# DDR3L.net
KiCad netlist of a schematic drawn in Altium Designer
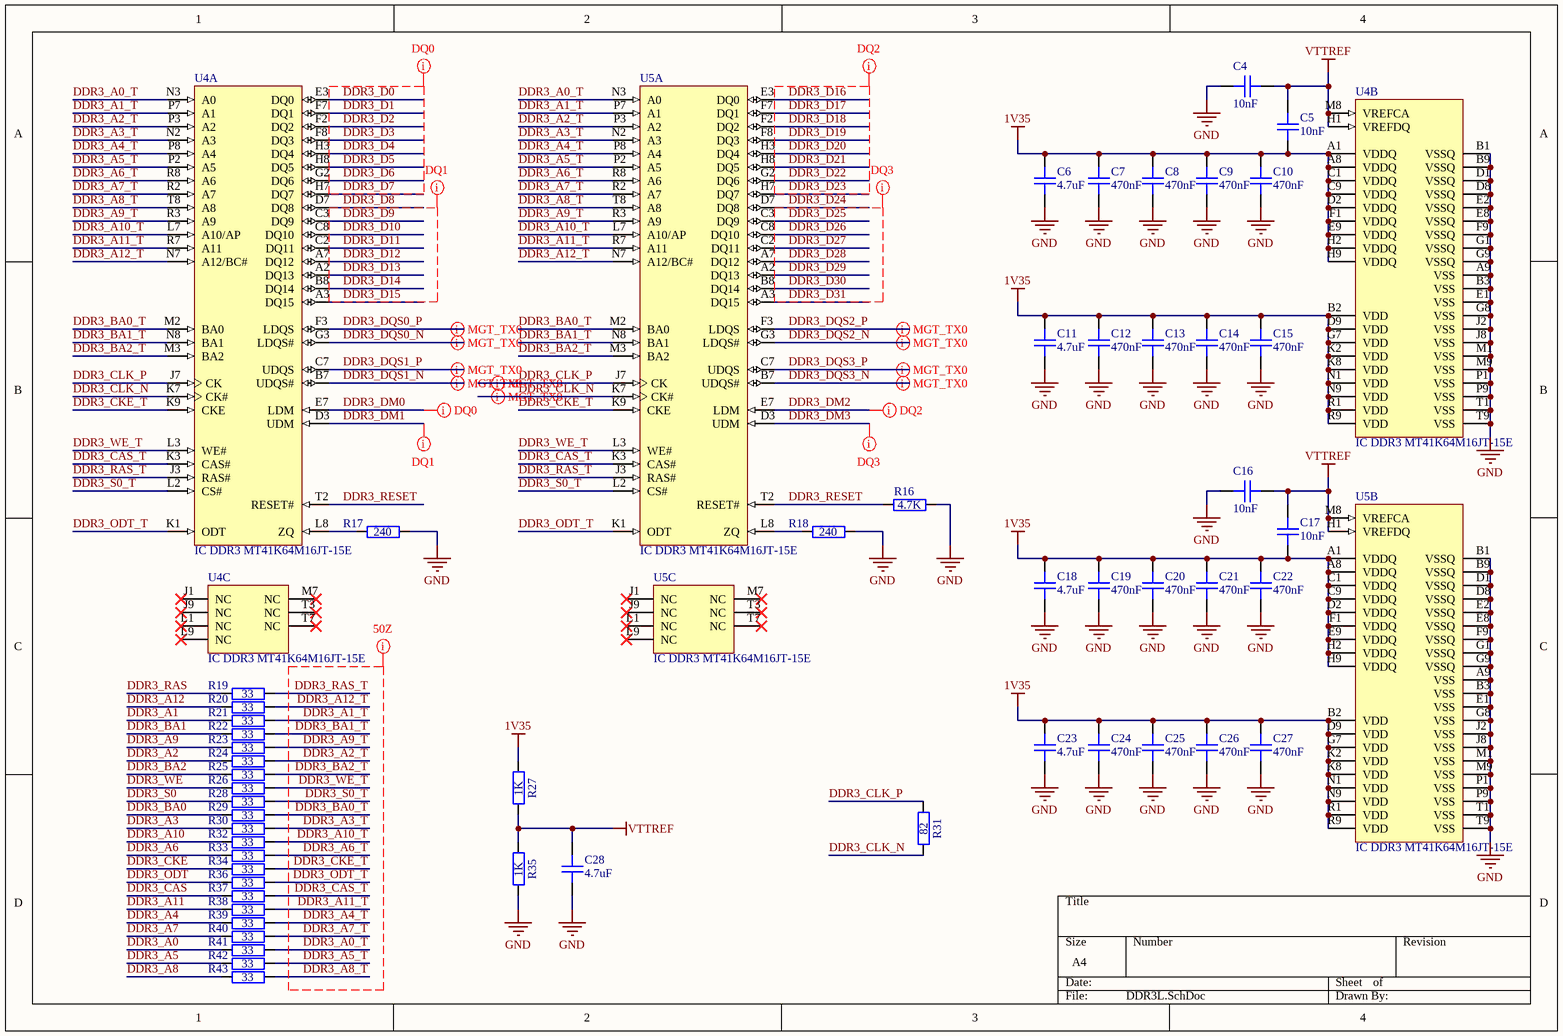
[diagram p0: DDR3L.SchDoc]

(export (version "E")
  (design (tool "Eeschema 10.0.6"))
  (components
    (comp (ref "C4")
      (value "10nF")
      (footprint "GEN_C_0402")
      (libsource (lib "DSO") (part "CAP 10nF 50V X7R 0402"))
    )
    (comp (ref "C5")
      (value "10nF")
      (footprint "GEN_C_0402")
      (libsource (lib "DSO") (part "CAP 10nF 50V X7R 0402"))
    )
    (comp (ref "C6")
      (value "4.7uF")
      (footprint "GEN_C_0402")
      (libsource (lib "DSO") (part "CAP 4.7uF 6.3V X5R 0402"))
    )
    (comp (ref "C7")
      (value "470nF")
      (footprint "GEN_C_0201")
      (libsource (lib "DSO") (part "CAP 470nF 6.3V X5R 0201"))
    )
    (comp (ref "C8")
      (value "470nF")
      (footprint "GEN_C_0201")
      (libsource (lib "DSO") (part "CAP 470nF 6.3V X5R 0201"))
    )
    (comp (ref "C9")
      (value "470nF")
      (footprint "GEN_C_0201")
      (libsource (lib "DSO") (part "CAP 470nF 6.3V X5R 0201"))
    )
    (comp (ref "C10")
      (value "470nF")
      (footprint "GEN_C_0201")
      (libsource (lib "DSO") (part "CAP 470nF 6.3V X5R 0201"))
    )
    (comp (ref "C11")
      (value "4.7uF")
      (footprint "GEN_C_0402")
      (libsource (lib "DSO") (part "CAP 4.7uF 6.3V X5R 0402"))
    )
    (comp (ref "C12")
      (value "470nF")
      (footprint "GEN_C_0201")
      (libsource (lib "DSO") (part "CAP 470nF 6.3V X5R 0201"))
    )
    (comp (ref "C13")
      (value "470nF")
      (footprint "GEN_C_0201")
      (libsource (lib "DSO") (part "CAP 470nF 6.3V X5R 0201"))
    )
    (comp (ref "C14")
      (value "470nF")
      (footprint "GEN_C_0201")
      (libsource (lib "DSO") (part "CAP 470nF 6.3V X5R 0201"))
    )
    (comp (ref "C15")
      (value "470nF")
      (footprint "GEN_C_0201")
      (libsource (lib "DSO") (part "CAP 470nF 6.3V X5R 0201"))
    )
    (comp (ref "C16")
      (value "10nF")
      (footprint "GEN_C_0402")
      (libsource (lib "DSO") (part "CAP 10nF 50V X7R 0402"))
    )
    (comp (ref "C17")
      (value "10nF")
      (footprint "GEN_C_0402")
      (libsource (lib "DSO") (part "CAP 10nF 50V X7R 0402"))
    )
    (comp (ref "C18")
      (value "4.7uF")
      (footprint "GEN_C_0402")
      (libsource (lib "DSO") (part "CAP 4.7uF 6.3V X5R 0402"))
    )
    (comp (ref "C19")
      (value "470nF")
      (footprint "GEN_C_0201")
      (libsource (lib "DSO") (part "CAP 470nF 6.3V X5R 0201"))
    )
    (comp (ref "C20")
      (value "470nF")
      (footprint "GEN_C_0201")
      (libsource (lib "DSO") (part "CAP 470nF 6.3V X5R 0201"))
    )
    (comp (ref "C21")
      (value "470nF")
      (footprint "GEN_C_0201")
      (libsource (lib "DSO") (part "CAP 470nF 6.3V X5R 0201"))
    )
    (comp (ref "C22")
      (value "470nF")
      (footprint "GEN_C_0201")
      (libsource (lib "DSO") (part "CAP 470nF 6.3V X5R 0201"))
    )
    (comp (ref "C23")
      (value "4.7uF")
      (footprint "GEN_C_0402")
      (libsource (lib "DSO") (part "CAP 4.7uF 6.3V X5R 0402"))
    )
    (comp (ref "C24")
      (value "470nF")
      (footprint "GEN_C_0201")
      (libsource (lib "DSO") (part "CAP 470nF 6.3V X5R 0201"))
    )
    (comp (ref "C25")
      (value "470nF")
      (footprint "GEN_C_0201")
      (libsource (lib "DSO") (part "CAP 470nF 6.3V X5R 0201"))
    )
    (comp (ref "C26")
      (value "470nF")
      (footprint "GEN_C_0201")
      (libsource (lib "DSO") (part "CAP 470nF 6.3V X5R 0201"))
    )
    (comp (ref "C27")
      (value "470nF")
      (footprint "GEN_C_0201")
      (libsource (lib "DSO") (part "CAP 470nF 6.3V X5R 0201"))
    )
    (comp (ref "C28")
      (value "4.7uF")
      (footprint "GEN_C_0402")
      (libsource (lib "DSO") (part "CAP 4.7uF 6.3V X5R 0402"))
    )
    (comp (ref "R16")
      (value "4.7K")
      (footprint "GEN_R_0201")
      (fields (field (name "TOLERANCE") "1%"))
      (libsource (lib "DSO") (part "RES 4.7K OHM 1% 1/20W 0201"))
    )
    (comp (ref "R17")
      (value "240")
      (footprint "GEN_R_0402")
      (fields (field (name "TOLERANCE") "1%"))
      (libsource (lib "DSO") (part "RES 240 OHM 1% 1/16W 0402"))
    )
    (comp (ref "R18")
      (value "240")
      (footprint "GEN_R_0402")
      (fields (field (name "TOLERANCE") "1%"))
      (libsource (lib "DSO") (part "RES 240 OHM 1% 1/16W 0402"))
    )
    (comp (ref "R19")
      (value "33")
      (footprint "GEN_R_0201")
      (fields (field (name "TOLERANCE") "1%"))
      (libsource (lib "DSO") (part "RES 33 OHM 1% 1/20W 0201"))
    )
    (comp (ref "R20")
      (value "33")
      (footprint "GEN_R_0201")
      (fields (field (name "TOLERANCE") "1%"))
      (libsource (lib "DSO") (part "RES 33 OHM 1% 1/20W 0201"))
    )
    (comp (ref "R21")
      (value "33")
      (footprint "GEN_R_0201")
      (fields (field (name "TOLERANCE") "1%"))
      (libsource (lib "DSO") (part "RES 33 OHM 1% 1/20W 0201"))
    )
    (comp (ref "R22")
      (value "33")
      (footprint "GEN_R_0201")
      (fields (field (name "TOLERANCE") "1%"))
      (libsource (lib "DSO") (part "RES 33 OHM 1% 1/20W 0201"))
    )
    (comp (ref "R23")
      (value "33")
      (footprint "GEN_R_0201")
      (fields (field (name "TOLERANCE") "1%"))
      (libsource (lib "DSO") (part "RES 33 OHM 1% 1/20W 0201"))
    )
    (comp (ref "R24")
      (value "33")
      (footprint "GEN_R_0201")
      (fields (field (name "TOLERANCE") "1%"))
      (libsource (lib "DSO") (part "RES 33 OHM 1% 1/20W 0201"))
    )
    (comp (ref "R25")
      (value "33")
      (footprint "GEN_R_0201")
      (fields (field (name "TOLERANCE") "1%"))
      (libsource (lib "DSO") (part "RES 33 OHM 1% 1/20W 0201"))
    )
    (comp (ref "R26")
      (value "33")
      (footprint "GEN_R_0201")
      (fields (field (name "TOLERANCE") "1%"))
      (libsource (lib "DSO") (part "RES 33 OHM 1% 1/20W 0201"))
    )
    (comp (ref "R27")
      (value "1K")
      (footprint "GEN_R_0402")
      (fields (field (name "TOLERANCE") "1%"))
      (libsource (lib "DSO") (part "RES 1K OHM 1% 1/10W 0402"))
    )
    (comp (ref "R28")
      (value "33")
      (footprint "GEN_R_0201")
      (fields (field (name "TOLERANCE") "1%"))
      (libsource (lib "DSO") (part "RES 33 OHM 1% 1/20W 0201"))
    )
    (comp (ref "R29")
      (value "33")
      (footprint "GEN_R_0201")
      (fields (field (name "TOLERANCE") "1%"))
      (libsource (lib "DSO") (part "RES 33 OHM 1% 1/20W 0201"))
    )
    (comp (ref "R30")
      (value "33")
      (footprint "GEN_R_0201")
      (fields (field (name "TOLERANCE") "1%"))
      (libsource (lib "DSO") (part "RES 33 OHM 1% 1/20W 0201"))
    )
    (comp (ref "R31")
      (value "82")
      (footprint "GEN_R_0402")
      (fields (field (name "TOLERANCE") "1%"))
      (libsource (lib "DSO") (part "RES 82 OHM 1% 1/16W 0402"))
    )
    (comp (ref "R32")
      (value "33")
      (footprint "GEN_R_0201")
      (fields (field (name "TOLERANCE") "1%"))
      (libsource (lib "DSO") (part "RES 33 OHM 1% 1/20W 0201"))
    )
    (comp (ref "R33")
      (value "33")
      (footprint "GEN_R_0201")
      (fields (field (name "TOLERANCE") "1%"))
      (libsource (lib "DSO") (part "RES 33 OHM 1% 1/20W 0201"))
    )
    (comp (ref "R34")
      (value "33")
      (footprint "GEN_R_0201")
      (fields (field (name "TOLERANCE") "1%"))
      (libsource (lib "DSO") (part "RES 33 OHM 1% 1/20W 0201"))
    )
    (comp (ref "R35")
      (value "1K")
      (footprint "GEN_R_0402")
      (fields (field (name "TOLERANCE") "1%"))
      (libsource (lib "DSO") (part "RES 1K OHM 1% 1/10W 0402"))
    )
    (comp (ref "R36")
      (value "33")
      (footprint "GEN_R_0201")
      (fields (field (name "TOLERANCE") "1%"))
      (libsource (lib "DSO") (part "RES 33 OHM 1% 1/20W 0201"))
    )
    (comp (ref "R37")
      (value "33")
      (footprint "GEN_R_0201")
      (fields (field (name "TOLERANCE") "1%"))
      (libsource (lib "DSO") (part "RES 33 OHM 1% 1/20W 0201"))
    )
    (comp (ref "R38")
      (value "33")
      (footprint "GEN_R_0201")
      (fields (field (name "TOLERANCE") "1%"))
      (libsource (lib "DSO") (part "RES 33 OHM 1% 1/20W 0201"))
    )
    (comp (ref "R39")
      (value "33")
      (footprint "GEN_R_0201")
      (fields (field (name "TOLERANCE") "1%"))
      (libsource (lib "DSO") (part "RES 33 OHM 1% 1/20W 0201"))
    )
    (comp (ref "R40")
      (value "33")
      (footprint "GEN_R_0201")
      (fields (field (name "TOLERANCE") "1%"))
      (libsource (lib "DSO") (part "RES 33 OHM 1% 1/20W 0201"))
    )
    (comp (ref "R41")
      (value "33")
      (footprint "GEN_R_0201")
      (fields (field (name "TOLERANCE") "1%"))
      (libsource (lib "DSO") (part "RES 33 OHM 1% 1/20W 0201"))
    )
    (comp (ref "R42")
      (value "33")
      (footprint "GEN_R_0201")
      (fields (field (name "TOLERANCE") "1%"))
      (libsource (lib "DSO") (part "RES 33 OHM 1% 1/20W 0201"))
    )
    (comp (ref "R43")
      (value "33")
      (footprint "GEN_R_0201")
      (fields (field (name "TOLERANCE") "1%"))
      (libsource (lib "DSO") (part "RES 33 OHM 1% 1/20W 0201"))
    )
    (comp (ref "U4")
      (value "IC DDR3 MT41K64M16JT-15E")
      (footprint "MICT-JT-96")
      (description "1Gb DDR3-1333 SDRAM, 64Mb x 16, 1.5ns, 1.35V, 0 to 95 degC, 96-Ball FBGA, Pb-Free")
      (fields (field (name "VOLTAGE") "1.35V") (field (name "MANUFACTURER") "Micron"))
      (libsource (lib "DSO") (part "IC DDR3 MT41K64M16JT-15E"))
    )
    (comp (ref "U5")
      (value "IC DDR3 MT41K64M16JT-15E")
      (footprint "MICT-JT-96")
      (description "1Gb DDR3-1333 SDRAM, 64Mb x 16, 1.5ns, 1.35V, 0 to 95 degC, 96-Ball FBGA, Pb-Free")
      (fields (field (name "VOLTAGE") "1.35V") (field (name "MANUFACTURER") "Micron"))
      (libsource (lib "DSO") (part "IC DDR3 MT41K64M16JT-15E"))
    )
  )
  (nets
    (net (code "1") (name "/DDR3_A0") (class "Default")
      (node (ref "R41") (pin "1") (pinfunction "1_1") (pintype "passive"))
    )
    (net (code "2") (name "/DDR3_A0_T") (class "Default")
      (node (ref "R41") (pin "2") (pinfunction "2_2") (pintype "passive"))
      (node (ref "U4") (pin "N3") (pinfunction "A0_N3") (pintype "input"))
      (node (ref "U5") (pin "N3") (pinfunction "A0_N3") (pintype "input"))
    )
    (net (code "3") (name "/DDR3_A1") (class "Default")
      (node (ref "R21") (pin "1") (pinfunction "1_1") (pintype "passive"))
    )
    (net (code "4") (name "/DDR3_A1_T") (class "Default")
      (node (ref "R21") (pin "2") (pinfunction "2_2") (pintype "passive"))
      (node (ref "U4") (pin "P7") (pinfunction "A1_P7") (pintype "input"))
      (node (ref "U5") (pin "P7") (pinfunction "A1_P7") (pintype "input"))
    )
    (net (code "5") (name "/DDR3_A2") (class "Default")
      (node (ref "R24") (pin "1") (pinfunction "1_1") (pintype "passive"))
    )
    (net (code "6") (name "/DDR3_A2_T") (class "Default")
      (node (ref "R24") (pin "2") (pinfunction "2_2") (pintype "passive"))
      (node (ref "U4") (pin "P3") (pinfunction "A2_P3") (pintype "input"))
      (node (ref "U5") (pin "P3") (pinfunction "A2_P3") (pintype "input"))
    )
    (net (code "7") (name "/DDR3_A3") (class "Default")
      (node (ref "R30") (pin "1") (pinfunction "1_1") (pintype "passive"))
    )
    (net (code "8") (name "/DDR3_A3_T") (class "Default")
      (node (ref "R30") (pin "2") (pinfunction "2_2") (pintype "passive"))
      (node (ref "U4") (pin "N2") (pinfunction "A3_N2") (pintype "input"))
      (node (ref "U5") (pin "N2") (pinfunction "A3_N2") (pintype "input"))
    )
    (net (code "9") (name "/DDR3_A4") (class "Default")
      (node (ref "R39") (pin "1") (pinfunction "1_1") (pintype "passive"))
    )
    (net (code "10") (name "/DDR3_A4_T") (class "Default")
      (node (ref "R39") (pin "2") (pinfunction "2_2") (pintype "passive"))
      (node (ref "U4") (pin "P8") (pinfunction "A4_P8") (pintype "input"))
      (node (ref "U5") (pin "P8") (pinfunction "A4_P8") (pintype "input"))
    )
    (net (code "11") (name "/DDR3_A5") (class "Default")
      (node (ref "R42") (pin "1") (pinfunction "1_1") (pintype "passive"))
    )
    (net (code "12") (name "/DDR3_A5_T") (class "Default")
      (node (ref "R42") (pin "2") (pinfunction "2_2") (pintype "passive"))
      (node (ref "U4") (pin "P2") (pinfunction "A5_P2") (pintype "input"))
      (node (ref "U5") (pin "P2") (pinfunction "A5_P2") (pintype "input"))
    )
    (net (code "13") (name "/DDR3_A6") (class "Default")
      (node (ref "R33") (pin "1") (pinfunction "1_1") (pintype "passive"))
    )
    (net (code "14") (name "/DDR3_A6_T") (class "Default")
      (node (ref "R33") (pin "2") (pinfunction "2_2") (pintype "passive"))
      (node (ref "U4") (pin "R8") (pinfunction "A6_R8") (pintype "input"))
      (node (ref "U5") (pin "R8") (pinfunction "A6_R8") (pintype "input"))
    )
    (net (code "15") (name "/DDR3_A7") (class "Default")
      (node (ref "R40") (pin "1") (pinfunction "1_1") (pintype "passive"))
    )
    (net (code "16") (name "/DDR3_A7_T") (class "Default")
      (node (ref "R40") (pin "2") (pinfunction "2_2") (pintype "passive"))
      (node (ref "U4") (pin "R2") (pinfunction "A7_R2") (pintype "input"))
      (node (ref "U5") (pin "R2") (pinfunction "A7_R2") (pintype "input"))
    )
    (net (code "17") (name "/DDR3_A8") (class "Default")
      (node (ref "R43") (pin "1") (pinfunction "1_1") (pintype "passive"))
    )
    (net (code "18") (name "/DDR3_A8_T") (class "Default")
      (node (ref "R43") (pin "2") (pinfunction "2_2") (pintype "passive"))
      (node (ref "U4") (pin "T8") (pinfunction "A8_T8") (pintype "input"))
      (node (ref "U5") (pin "T8") (pinfunction "A8_T8") (pintype "input"))
    )
    (net (code "19") (name "/DDR3_A9") (class "Default")
      (node (ref "R23") (pin "1") (pinfunction "1_1") (pintype "passive"))
    )
    (net (code "20") (name "/DDR3_A9_T") (class "Default")
      (node (ref "R23") (pin "2") (pinfunction "2_2") (pintype "passive"))
      (node (ref "U4") (pin "R3") (pinfunction "A9_R3") (pintype "input"))
      (node (ref "U5") (pin "R3") (pinfunction "A9_R3") (pintype "input"))
    )
    (net (code "21") (name "/DDR3_A10") (class "Default")
      (node (ref "R32") (pin "1") (pinfunction "1_1") (pintype "passive"))
    )
    (net (code "22") (name "/DDR3_A10_T") (class "Default")
      (node (ref "R32") (pin "2") (pinfunction "2_2") (pintype "passive"))
      (node (ref "U4") (pin "L7") (pinfunction "A10/AP_L7") (pintype "input"))
      (node (ref "U5") (pin "L7") (pinfunction "A10/AP_L7") (pintype "input"))
    )
    (net (code "23") (name "/DDR3_A11") (class "Default")
      (node (ref "R38") (pin "1") (pinfunction "1_1") (pintype "passive"))
    )
    (net (code "24") (name "/DDR3_A11_T") (class "Default")
      (node (ref "R38") (pin "2") (pinfunction "2_2") (pintype "passive"))
      (node (ref "U4") (pin "R7") (pinfunction "A11_R7") (pintype "input"))
      (node (ref "U5") (pin "R7") (pinfunction "A11_R7") (pintype "input"))
    )
    (net (code "25") (name "/DDR3_A12") (class "Default")
      (node (ref "R20") (pin "1") (pinfunction "1_1") (pintype "passive"))
    )
    (net (code "26") (name "/DDR3_A12_T") (class "Default")
      (node (ref "R20") (pin "2") (pinfunction "2_2") (pintype "passive"))
      (node (ref "U4") (pin "N7") (pinfunction "A12/BC#_N7") (pintype "input"))
      (node (ref "U5") (pin "N7") (pinfunction "A12/BC#_N7") (pintype "input"))
    )
    (net (code "27") (name "/DDR3_BA0") (class "Default")
      (node (ref "R29") (pin "1") (pinfunction "1_1") (pintype "passive"))
    )
    (net (code "28") (name "/DDR3_BA0_T") (class "Default")
      (node (ref "R29") (pin "2") (pinfunction "2_2") (pintype "passive"))
      (node (ref "U4") (pin "M2") (pinfunction "BA0_M2") (pintype "input"))
      (node (ref "U5") (pin "M2") (pinfunction "BA0_M2") (pintype "input"))
    )
    (net (code "29") (name "/DDR3_BA1") (class "Default")
      (node (ref "R22") (pin "1") (pinfunction "1_1") (pintype "passive"))
    )
    (net (code "30") (name "/DDR3_BA1_T") (class "Default")
      (node (ref "R22") (pin "2") (pinfunction "2_2") (pintype "passive"))
      (node (ref "U4") (pin "N8") (pinfunction "BA1_N8") (pintype "input"))
      (node (ref "U5") (pin "N8") (pinfunction "BA1_N8") (pintype "input"))
    )
    (net (code "31") (name "/DDR3_BA2") (class "Default")
      (node (ref "R25") (pin "1") (pinfunction "1_1") (pintype "passive"))
    )
    (net (code "32") (name "/DDR3_BA2_T") (class "Default")
      (node (ref "R25") (pin "2") (pinfunction "2_2") (pintype "passive"))
      (node (ref "U4") (pin "M3") (pinfunction "BA2_M3") (pintype "input"))
      (node (ref "U5") (pin "M3") (pinfunction "BA2_M3") (pintype "input"))
    )
    (net (code "33") (name "/DDR3_CAS") (class "Default")
      (node (ref "R37") (pin "1") (pinfunction "1_1") (pintype "passive"))
    )
    (net (code "34") (name "/DDR3_CAS_T") (class "Default")
      (node (ref "R37") (pin "2") (pinfunction "2_2") (pintype "passive"))
      (node (ref "U4") (pin "K3") (pinfunction "CAS#_K3") (pintype "input"))
      (node (ref "U5") (pin "K3") (pinfunction "CAS#_K3") (pintype "input"))
    )
    (net (code "35") (name "/DDR3_CKE") (class "Default")
      (node (ref "R34") (pin "1") (pinfunction "1_1") (pintype "passive"))
    )
    (net (code "36") (name "/DDR3_CKE_T") (class "Default")
      (node (ref "R34") (pin "2") (pinfunction "2_2") (pintype "passive"))
      (node (ref "U4") (pin "K9") (pinfunction "CKE_K9") (pintype "input"))
      (node (ref "U5") (pin "K9") (pinfunction "CKE_K9") (pintype "input"))
    )
    (net (code "37") (name "/DDR3_CLK_N") (class "Default")
      (node (ref "R31") (pin "1") (pinfunction "1_1") (pintype "passive"))
      (node (ref "U4") (pin "K7") (pinfunction "CK#_K7") (pintype "input"))
      (node (ref "U5") (pin "K7") (pinfunction "CK#_K7") (pintype "input"))
    )
    (net (code "38") (name "/DDR3_CLK_P") (class "Default")
      (node (ref "R31") (pin "2") (pinfunction "2_2") (pintype "passive"))
      (node (ref "U4") (pin "J7") (pinfunction "CK_J7") (pintype "input"))
      (node (ref "U5") (pin "J7") (pinfunction "CK_J7") (pintype "input"))
    )
    (net (code "39") (name "/DDR3_D0") (class "Default")
      (node (ref "U4") (pin "E3") (pinfunction "DQ0_E3") (pintype "bidirectional"))
    )
    (net (code "40") (name "/DDR3_D1") (class "Default")
      (node (ref "U4") (pin "F7") (pinfunction "DQ1_F7") (pintype "bidirectional"))
    )
    (net (code "41") (name "/DDR3_D2") (class "Default")
      (node (ref "U4") (pin "F2") (pinfunction "DQ2_F2") (pintype "bidirectional"))
    )
    (net (code "42") (name "/DDR3_D3") (class "Default")
      (node (ref "U4") (pin "F8") (pinfunction "DQ3_F8") (pintype "bidirectional"))
    )
    (net (code "43") (name "/DDR3_D4") (class "Default")
      (node (ref "U4") (pin "H3") (pinfunction "DQ4_H3") (pintype "bidirectional"))
    )
    (net (code "44") (name "/DDR3_D5") (class "Default")
      (node (ref "U4") (pin "H8") (pinfunction "DQ5_H8") (pintype "bidirectional"))
    )
    (net (code "45") (name "/DDR3_D6") (class "Default")
      (node (ref "U4") (pin "G2") (pinfunction "DQ6_G2") (pintype "bidirectional"))
    )
    (net (code "46") (name "/DDR3_D7") (class "Default")
      (node (ref "U4") (pin "H7") (pinfunction "DQ7_H7") (pintype "bidirectional"))
    )
    (net (code "47") (name "/DDR3_D8") (class "Default")
      (node (ref "U4") (pin "D7") (pinfunction "DQ8_D7") (pintype "bidirectional"))
    )
    (net (code "48") (name "/DDR3_D9") (class "Default")
      (node (ref "U4") (pin "C3") (pinfunction "DQ9_C3") (pintype "bidirectional"))
    )
    (net (code "49") (name "/DDR3_D10") (class "Default")
      (node (ref "U4") (pin "C8") (pinfunction "DQ10_C8") (pintype "bidirectional"))
    )
    (net (code "50") (name "/DDR3_D11") (class "Default")
      (node (ref "U4") (pin "C2") (pinfunction "DQ11_C2") (pintype "bidirectional"))
    )
    (net (code "51") (name "/DDR3_D12") (class "Default")
      (node (ref "U4") (pin "A7") (pinfunction "DQ12_A7") (pintype "bidirectional"))
    )
    (net (code "52") (name "/DDR3_D13") (class "Default")
      (node (ref "U4") (pin "A2") (pinfunction "DQ13_A2") (pintype "bidirectional"))
    )
    (net (code "53") (name "/DDR3_D14") (class "Default")
      (node (ref "U4") (pin "B8") (pinfunction "DQ14_B8") (pintype "bidirectional"))
    )
    (net (code "54") (name "/DDR3_D15") (class "Default")
      (node (ref "U4") (pin "A3") (pinfunction "DQ15_A3") (pintype "bidirectional"))
    )
    (net (code "55") (name "/DDR3_D16") (class "Default")
      (node (ref "U5") (pin "E3") (pinfunction "DQ0_E3") (pintype "bidirectional"))
    )
    (net (code "56") (name "/DDR3_D17") (class "Default")
      (node (ref "U5") (pin "F7") (pinfunction "DQ1_F7") (pintype "bidirectional"))
    )
    (net (code "57") (name "/DDR3_D18") (class "Default")
      (node (ref "U5") (pin "F2") (pinfunction "DQ2_F2") (pintype "bidirectional"))
    )
    (net (code "58") (name "/DDR3_D19") (class "Default")
      (node (ref "U5") (pin "F8") (pinfunction "DQ3_F8") (pintype "bidirectional"))
    )
    (net (code "59") (name "/DDR3_D20") (class "Default")
      (node (ref "U5") (pin "H3") (pinfunction "DQ4_H3") (pintype "bidirectional"))
    )
    (net (code "60") (name "/DDR3_D21") (class "Default")
      (node (ref "U5") (pin "H8") (pinfunction "DQ5_H8") (pintype "bidirectional"))
    )
    (net (code "61") (name "/DDR3_D22") (class "Default")
      (node (ref "U5") (pin "G2") (pinfunction "DQ6_G2") (pintype "bidirectional"))
    )
    (net (code "62") (name "/DDR3_D23") (class "Default")
      (node (ref "U5") (pin "H7") (pinfunction "DQ7_H7") (pintype "bidirectional"))
    )
    (net (code "63") (name "/DDR3_D24") (class "Default")
      (node (ref "U5") (pin "D7") (pinfunction "DQ8_D7") (pintype "bidirectional"))
    )
    (net (code "64") (name "/DDR3_D25") (class "Default")
      (node (ref "U5") (pin "C3") (pinfunction "DQ9_C3") (pintype "bidirectional"))
    )
    (net (code "65") (name "/DDR3_D26") (class "Default")
      (node (ref "U5") (pin "C8") (pinfunction "DQ10_C8") (pintype "bidirectional"))
    )
    (net (code "66") (name "/DDR3_D27") (class "Default")
      (node (ref "U5") (pin "C2") (pinfunction "DQ11_C2") (pintype "bidirectional"))
    )
    (net (code "67") (name "/DDR3_D28") (class "Default")
      (node (ref "U5") (pin "A7") (pinfunction "DQ12_A7") (pintype "bidirectional"))
    )
    (net (code "68") (name "/DDR3_D29") (class "Default")
      (node (ref "U5") (pin "A2") (pinfunction "DQ13_A2") (pintype "bidirectional"))
    )
    (net (code "69") (name "/DDR3_D30") (class "Default")
      (node (ref "U5") (pin "B8") (pinfunction "DQ14_B8") (pintype "bidirectional"))
    )
    (net (code "70") (name "/DDR3_D31") (class "Default")
      (node (ref "U5") (pin "A3") (pinfunction "DQ15_A3") (pintype "bidirectional"))
    )
    (net (code "71") (name "/DDR3_DM0") (class "Default")
      (node (ref "U4") (pin "E7") (pinfunction "LDM_E7") (pintype "input"))
    )
    (net (code "72") (name "/DDR3_DM1") (class "Default")
      (node (ref "U4") (pin "D3") (pinfunction "UDM_D3") (pintype "input"))
    )
    (net (code "73") (name "/DDR3_DM2") (class "Default")
      (node (ref "U5") (pin "E7") (pinfunction "LDM_E7") (pintype "input"))
    )
    (net (code "74") (name "/DDR3_DM3") (class "Default")
      (node (ref "U5") (pin "D3") (pinfunction "UDM_D3") (pintype "input"))
    )
    (net (code "75") (name "/DDR3_DQS0_N") (class "Default")
      (node (ref "U4") (pin "G3") (pinfunction "LDQS#_G3") (pintype "bidirectional"))
    )
    (net (code "76") (name "/DDR3_DQS0_P") (class "Default")
      (node (ref "U4") (pin "F3") (pinfunction "LDQS_F3") (pintype "bidirectional"))
    )
    (net (code "77") (name "/DDR3_DQS1_N") (class "Default")
      (node (ref "U4") (pin "B7") (pinfunction "UDQS#_B7") (pintype "bidirectional"))
    )
    (net (code "78") (name "/DDR3_DQS1_P") (class "Default")
      (node (ref "U4") (pin "C7") (pinfunction "UDQS_C7") (pintype "bidirectional"))
    )
    (net (code "79") (name "/DDR3_DQS2_N") (class "Default")
      (node (ref "U5") (pin "G3") (pinfunction "LDQS#_G3") (pintype "bidirectional"))
    )
    (net (code "80") (name "/DDR3_DQS2_P") (class "Default")
      (node (ref "U5") (pin "F3") (pinfunction "LDQS_F3") (pintype "bidirectional"))
    )
    (net (code "81") (name "/DDR3_DQS3_N") (class "Default")
      (node (ref "U5") (pin "B7") (pinfunction "UDQS#_B7") (pintype "bidirectional"))
    )
    (net (code "82") (name "/DDR3_DQS3_P") (class "Default")
      (node (ref "U5") (pin "C7") (pinfunction "UDQS_C7") (pintype "bidirectional"))
    )
    (net (code "83") (name "/DDR3_ODT") (class "Default")
      (node (ref "R36") (pin "1") (pinfunction "1_1") (pintype "passive"))
    )
    (net (code "84") (name "/DDR3_ODT_T") (class "Default")
      (node (ref "R36") (pin "2") (pinfunction "2_2") (pintype "passive"))
      (node (ref "U4") (pin "K1") (pinfunction "ODT_K1") (pintype "input"))
      (node (ref "U5") (pin "K1") (pinfunction "ODT_K1") (pintype "input"))
    )
    (net (code "85") (name "/DDR3_RAS") (class "Default")
      (node (ref "R19") (pin "1") (pinfunction "1_1") (pintype "passive"))
    )
    (net (code "86") (name "/DDR3_RAS_T") (class "Default")
      (node (ref "R19") (pin "2") (pinfunction "2_2") (pintype "passive"))
      (node (ref "U4") (pin "J3") (pinfunction "RAS#_J3") (pintype "input"))
      (node (ref "U5") (pin "J3") (pinfunction "RAS#_J3") (pintype "input"))
    )
    (net (code "87") (name "/DDR3_RESET") (class "Default")
      (node (ref "R16") (pin "1") (pinfunction "1_1") (pintype "passive"))
      (node (ref "U4") (pin "T2") (pinfunction "RESET#_T2") (pintype "input"))
      (node (ref "U5") (pin "T2") (pinfunction "RESET#_T2") (pintype "input"))
    )
    (net (code "88") (name "/DDR3_S0") (class "Default")
      (node (ref "R28") (pin "1") (pinfunction "1_1") (pintype "passive"))
    )
    (net (code "89") (name "/DDR3_S0_T") (class "Default")
      (node (ref "R28") (pin "2") (pinfunction "2_2") (pintype "passive"))
      (node (ref "U4") (pin "L2") (pinfunction "CS#_L2") (pintype "input"))
      (node (ref "U5") (pin "L2") (pinfunction "CS#_L2") (pintype "input"))
    )
    (net (code "90") (name "/DDR3_WE") (class "Default")
      (node (ref "R26") (pin "1") (pinfunction "1_1") (pintype "passive"))
    )
    (net (code "91") (name "/DDR3_WE_T") (class "Default")
      (node (ref "R26") (pin "2") (pinfunction "2_2") (pintype "passive"))
      (node (ref "U4") (pin "L3") (pinfunction "WE#_L3") (pintype "input"))
      (node (ref "U5") (pin "L3") (pinfunction "WE#_L3") (pintype "input"))
    )
    (net (code "92") (name "1V35") (class "Default")
      (node (ref "C10") (pin "2") (pinfunction "2_2") (pintype "passive"))
      (node (ref "C11") (pin "2") (pinfunction "2_2") (pintype "passive"))
      (node (ref "C12") (pin "2") (pinfunction "2_2") (pintype "passive"))
      (node (ref "C13") (pin "2") (pinfunction "2_2") (pintype "passive"))
      (node (ref "C14") (pin "2") (pinfunction "2_2") (pintype "passive"))
      (node (ref "C15") (pin "2") (pinfunction "2_2") (pintype "passive"))
      (node (ref "C17") (pin "2") (pinfunction "2_2") (pintype "passive"))
      (node (ref "C18") (pin "2") (pinfunction "2_2") (pintype "passive"))
      (node (ref "C19") (pin "2") (pinfunction "2_2") (pintype "passive"))
      (node (ref "C20") (pin "2") (pinfunction "2_2") (pintype "passive"))
      (node (ref "C21") (pin "2") (pinfunction "2_2") (pintype "passive"))
      (node (ref "C22") (pin "2") (pinfunction "2_2") (pintype "passive"))
      (node (ref "C23") (pin "2") (pinfunction "2_2") (pintype "passive"))
      (node (ref "C24") (pin "2") (pinfunction "2_2") (pintype "passive"))
      (node (ref "C25") (pin "2") (pinfunction "2_2") (pintype "passive"))
      (node (ref "C26") (pin "2") (pinfunction "2_2") (pintype "passive"))
      (node (ref "C27") (pin "2") (pinfunction "2_2") (pintype "passive"))
      (node (ref "C5") (pin "2") (pinfunction "2_2") (pintype "passive"))
      (node (ref "C6") (pin "2") (pinfunction "2_2") (pintype "passive"))
      (node (ref "C7") (pin "2") (pinfunction "2_2") (pintype "passive"))
      (node (ref "C8") (pin "2") (pinfunction "2_2") (pintype "passive"))
      (node (ref "C9") (pin "2") (pinfunction "2_2") (pintype "passive"))
      (node (ref "R27") (pin "2") (pinfunction "2_2") (pintype "passive"))
      (node (ref "U4") (pin "A1") (pinfunction "VDDQ_A1") (pintype "power_in"))
      (node (ref "U4") (pin "A8") (pinfunction "VDDQ_A8") (pintype "power_in"))
      (node (ref "U4") (pin "B2") (pinfunction "VDD_B2") (pintype "power_in"))
      (node (ref "U4") (pin "C1") (pinfunction "VDDQ_C1") (pintype "power_in"))
      (node (ref "U4") (pin "C9") (pinfunction "VDDQ_C9") (pintype "power_in"))
      (node (ref "U4") (pin "D2") (pinfunction "VDDQ_D2") (pintype "power_in"))
      (node (ref "U4") (pin "D9") (pinfunction "VDD_D9") (pintype "power_in"))
      (node (ref "U4") (pin "E9") (pinfunction "VDDQ_E9") (pintype "power_in"))
      (node (ref "U4") (pin "F1") (pinfunction "VDDQ_F1") (pintype "power_in"))
      (node (ref "U4") (pin "G7") (pinfunction "VDD_G7") (pintype "power_in"))
      (node (ref "U4") (pin "H2") (pinfunction "VDDQ_H2") (pintype "power_in"))
      (node (ref "U4") (pin "H9") (pinfunction "VDDQ_H9") (pintype "power_in"))
      (node (ref "U4") (pin "K2") (pinfunction "VDD_K2") (pintype "power_in"))
      (node (ref "U4") (pin "K8") (pinfunction "VDD_K8") (pintype "power_in"))
      (node (ref "U4") (pin "N1") (pinfunction "VDD_N1") (pintype "power_in"))
      (node (ref "U4") (pin "N9") (pinfunction "VDD_N9") (pintype "power_in"))
      (node (ref "U4") (pin "R1") (pinfunction "VDD_R1") (pintype "power_in"))
      (node (ref "U4") (pin "R9") (pinfunction "VDD_R9") (pintype "power_in"))
      (node (ref "U5") (pin "A1") (pinfunction "VDDQ_A1") (pintype "power_in"))
      (node (ref "U5") (pin "A8") (pinfunction "VDDQ_A8") (pintype "power_in"))
      (node (ref "U5") (pin "B2") (pinfunction "VDD_B2") (pintype "power_in"))
      (node (ref "U5") (pin "C1") (pinfunction "VDDQ_C1") (pintype "power_in"))
      (node (ref "U5") (pin "C9") (pinfunction "VDDQ_C9") (pintype "power_in"))
      (node (ref "U5") (pin "D2") (pinfunction "VDDQ_D2") (pintype "power_in"))
      (node (ref "U5") (pin "D9") (pinfunction "VDD_D9") (pintype "power_in"))
      (node (ref "U5") (pin "E9") (pinfunction "VDDQ_E9") (pintype "power_in"))
      (node (ref "U5") (pin "F1") (pinfunction "VDDQ_F1") (pintype "power_in"))
      (node (ref "U5") (pin "G7") (pinfunction "VDD_G7") (pintype "power_in"))
      (node (ref "U5") (pin "H2") (pinfunction "VDDQ_H2") (pintype "power_in"))
      (node (ref "U5") (pin "H9") (pinfunction "VDDQ_H9") (pintype "power_in"))
      (node (ref "U5") (pin "K2") (pinfunction "VDD_K2") (pintype "power_in"))
      (node (ref "U5") (pin "K8") (pinfunction "VDD_K8") (pintype "power_in"))
      (node (ref "U5") (pin "N1") (pinfunction "VDD_N1") (pintype "power_in"))
      (node (ref "U5") (pin "N9") (pinfunction "VDD_N9") (pintype "power_in"))
      (node (ref "U5") (pin "R1") (pinfunction "VDD_R1") (pintype "power_in"))
      (node (ref "U5") (pin "R9") (pinfunction "VDD_R9") (pintype "power_in"))
    )
    (net (code "93") (name "GND") (class "Default")
      (node (ref "C10") (pin "1") (pinfunction "1_1") (pintype "passive"))
      (node (ref "C11") (pin "1") (pinfunction "1_1") (pintype "passive"))
      (node (ref "C12") (pin "1") (pinfunction "1_1") (pintype "passive"))
      (node (ref "C13") (pin "1") (pinfunction "1_1") (pintype "passive"))
      (node (ref "C14") (pin "1") (pinfunction "1_1") (pintype "passive"))
      (node (ref "C15") (pin "1") (pinfunction "1_1") (pintype "passive"))
      (node (ref "C16") (pin "1") (pinfunction "1_1") (pintype "passive"))
      (node (ref "C18") (pin "1") (pinfunction "1_1") (pintype "passive"))
      (node (ref "C19") (pin "1") (pinfunction "1_1") (pintype "passive"))
      (node (ref "C20") (pin "1") (pinfunction "1_1") (pintype "passive"))
      (node (ref "C21") (pin "1") (pinfunction "1_1") (pintype "passive"))
      (node (ref "C22") (pin "1") (pinfunction "1_1") (pintype "passive"))
      (node (ref "C23") (pin "1") (pinfunction "1_1") (pintype "passive"))
      (node (ref "C24") (pin "1") (pinfunction "1_1") (pintype "passive"))
      (node (ref "C25") (pin "1") (pinfunction "1_1") (pintype "passive"))
      (node (ref "C26") (pin "1") (pinfunction "1_1") (pintype "passive"))
      (node (ref "C27") (pin "1") (pinfunction "1_1") (pintype "passive"))
      (node (ref "C28") (pin "1") (pinfunction "1_1") (pintype "passive"))
      (node (ref "C4") (pin "1") (pinfunction "1_1") (pintype "passive"))
      (node (ref "C6") (pin "1") (pinfunction "1_1") (pintype "passive"))
      (node (ref "C7") (pin "1") (pinfunction "1_1") (pintype "passive"))
      (node (ref "C8") (pin "1") (pinfunction "1_1") (pintype "passive"))
      (node (ref "C9") (pin "1") (pinfunction "1_1") (pintype "passive"))
      (node (ref "R16") (pin "2") (pinfunction "2_2") (pintype "passive"))
      (node (ref "R17") (pin "2") (pinfunction "2_2") (pintype "passive"))
      (node (ref "R18") (pin "2") (pinfunction "2_2") (pintype "passive"))
      (node (ref "R35") (pin "1") (pinfunction "1_1") (pintype "passive"))
      (node (ref "U4") (pin "A9") (pinfunction "VSS_A9") (pintype "power_in"))
      (node (ref "U4") (pin "B1") (pinfunction "VSSQ_B1") (pintype "power_in"))
      (node (ref "U4") (pin "B3") (pinfunction "VSS_B3") (pintype "power_in"))
      (node (ref "U4") (pin "B9") (pinfunction "VSSQ_B9") (pintype "power_in"))
      (node (ref "U4") (pin "D1") (pinfunction "VSSQ_D1") (pintype "power_in"))
      (node (ref "U4") (pin "D8") (pinfunction "VSSQ_D8") (pintype "power_in"))
      (node (ref "U4") (pin "E1") (pinfunction "VSS_E1") (pintype "power_in"))
      (node (ref "U4") (pin "E2") (pinfunction "VSSQ_E2") (pintype "power_in"))
      (node (ref "U4") (pin "E8") (pinfunction "VSSQ_E8") (pintype "power_in"))
      (node (ref "U4") (pin "F9") (pinfunction "VSSQ_F9") (pintype "power_in"))
      (node (ref "U4") (pin "G1") (pinfunction "VSSQ_G1") (pintype "power_in"))
      (node (ref "U4") (pin "G8") (pinfunction "VSS_G8") (pintype "power_in"))
      (node (ref "U4") (pin "G9") (pinfunction "VSSQ_G9") (pintype "power_in"))
      (node (ref "U4") (pin "J2") (pinfunction "VSS_J2") (pintype "power_in"))
      (node (ref "U4") (pin "J8") (pinfunction "VSS_J8") (pintype "power_in"))
      (node (ref "U4") (pin "M1") (pinfunction "VSS_M1") (pintype "power_in"))
      (node (ref "U4") (pin "M9") (pinfunction "VSS_M9") (pintype "power_in"))
      (node (ref "U4") (pin "P1") (pinfunction "VSS_P1") (pintype "power_in"))
      (node (ref "U4") (pin "P9") (pinfunction "VSS_P9") (pintype "power_in"))
      (node (ref "U4") (pin "T1") (pinfunction "VSS_T1") (pintype "power_in"))
      (node (ref "U4") (pin "T9") (pinfunction "VSS_T9") (pintype "power_in"))
      (node (ref "U5") (pin "A9") (pinfunction "VSS_A9") (pintype "power_in"))
      (node (ref "U5") (pin "B1") (pinfunction "VSSQ_B1") (pintype "power_in"))
      (node (ref "U5") (pin "B3") (pinfunction "VSS_B3") (pintype "power_in"))
      (node (ref "U5") (pin "B9") (pinfunction "VSSQ_B9") (pintype "power_in"))
      (node (ref "U5") (pin "D1") (pinfunction "VSSQ_D1") (pintype "power_in"))
      (node (ref "U5") (pin "D8") (pinfunction "VSSQ_D8") (pintype "power_in"))
      (node (ref "U5") (pin "E1") (pinfunction "VSS_E1") (pintype "power_in"))
      (node (ref "U5") (pin "E2") (pinfunction "VSSQ_E2") (pintype "power_in"))
      (node (ref "U5") (pin "E8") (pinfunction "VSSQ_E8") (pintype "power_in"))
      (node (ref "U5") (pin "F9") (pinfunction "VSSQ_F9") (pintype "power_in"))
      (node (ref "U5") (pin "G1") (pinfunction "VSSQ_G1") (pintype "power_in"))
      (node (ref "U5") (pin "G8") (pinfunction "VSS_G8") (pintype "power_in"))
      (node (ref "U5") (pin "G9") (pinfunction "VSSQ_G9") (pintype "power_in"))
      (node (ref "U5") (pin "J2") (pinfunction "VSS_J2") (pintype "power_in"))
      (node (ref "U5") (pin "J8") (pinfunction "VSS_J8") (pintype "power_in"))
      (node (ref "U5") (pin "M1") (pinfunction "VSS_M1") (pintype "power_in"))
      (node (ref "U5") (pin "M9") (pinfunction "VSS_M9") (pintype "power_in"))
      (node (ref "U5") (pin "P1") (pinfunction "VSS_P1") (pintype "power_in"))
      (node (ref "U5") (pin "P9") (pinfunction "VSS_P9") (pintype "power_in"))
      (node (ref "U5") (pin "T1") (pinfunction "VSS_T1") (pintype "power_in"))
      (node (ref "U5") (pin "T9") (pinfunction "VSS_T9") (pintype "power_in"))
    )
    (net (code "94") (name "Net-(U4A-ZQ)") (class "Default")
      (node (ref "R17") (pin "1") (pinfunction "1_1") (pintype "passive"))
      (node (ref "U4") (pin "L8") (pinfunction "ZQ_L8") (pintype "input"))
    )
    (net (code "95") (name "Net-(U5A-ZQ)") (class "Default")
      (node (ref "R18") (pin "1") (pinfunction "1_1") (pintype "passive"))
      (node (ref "U5") (pin "L8") (pinfunction "ZQ_L8") (pintype "input"))
    )
    (net (code "96") (name "VTTREF") (class "Default")
      (node (ref "C16") (pin "2") (pinfunction "2_2") (pintype "passive"))
      (node (ref "C17") (pin "1") (pinfunction "1_1") (pintype "passive"))
      (node (ref "C28") (pin "2") (pinfunction "2_2") (pintype "passive"))
      (node (ref "C4") (pin "2") (pinfunction "2_2") (pintype "passive"))
      (node (ref "C5") (pin "1") (pinfunction "1_1") (pintype "passive"))
      (node (ref "R27") (pin "1") (pinfunction "1_1") (pintype "passive"))
      (node (ref "R35") (pin "2") (pinfunction "2_2") (pintype "passive"))
      (node (ref "U4") (pin "H1") (pinfunction "VREFDQ_H1") (pintype "input"))
      (node (ref "U4") (pin "M8") (pinfunction "VREFCA_M8") (pintype "input"))
      (node (ref "U5") (pin "H1") (pinfunction "VREFDQ_H1") (pintype "input"))
      (node (ref "U5") (pin "M8") (pinfunction "VREFCA_M8") (pintype "input"))
    )
    (net (code "97") (name "unconnected-(U4C-NC-PadJ1)") (class "Default")
      (node (ref "U4") (pin "J1") (pinfunction "NC_J1") (pintype "passive+no_connect"))
    )
    (net (code "98") (name "unconnected-(U4C-NC-PadJ9)") (class "Default")
      (node (ref "U4") (pin "J9") (pinfunction "NC_J9") (pintype "passive+no_connect"))
    )
    (net (code "99") (name "unconnected-(U4C-NC-PadL1)") (class "Default")
      (node (ref "U4") (pin "L1") (pinfunction "NC_L1") (pintype "passive+no_connect"))
    )
    (net (code "100") (name "unconnected-(U4C-NC-PadL9)") (class "Default")
      (node (ref "U4") (pin "L9") (pinfunction "NC_L9") (pintype "passive+no_connect"))
    )
    (net (code "101") (name "unconnected-(U4C-NC-PadM7)") (class "Default")
      (node (ref "U4") (pin "M7") (pinfunction "NC_M7") (pintype "passive+no_connect"))
    )
    (net (code "102") (name "unconnected-(U4C-NC-PadT3)") (class "Default")
      (node (ref "U4") (pin "T3") (pinfunction "NC_T3") (pintype "passive+no_connect"))
    )
    (net (code "103") (name "unconnected-(U4C-NC-PadT7)") (class "Default")
      (node (ref "U4") (pin "T7") (pinfunction "NC_T7") (pintype "passive+no_connect"))
    )
    (net (code "104") (name "unconnected-(U5C-NC-PadJ1)") (class "Default")
      (node (ref "U5") (pin "J1") (pinfunction "NC_J1") (pintype "passive+no_connect"))
    )
    (net (code "105") (name "unconnected-(U5C-NC-PadJ9)") (class "Default")
      (node (ref "U5") (pin "J9") (pinfunction "NC_J9") (pintype "passive+no_connect"))
    )
    (net (code "106") (name "unconnected-(U5C-NC-PadL1)") (class "Default")
      (node (ref "U5") (pin "L1") (pinfunction "NC_L1") (pintype "passive+no_connect"))
    )
    (net (code "107") (name "unconnected-(U5C-NC-PadL9)") (class "Default")
      (node (ref "U5") (pin "L9") (pinfunction "NC_L9") (pintype "passive+no_connect"))
    )
    (net (code "108") (name "unconnected-(U5C-NC-PadM7)") (class "Default")
      (node (ref "U5") (pin "M7") (pinfunction "NC_M7") (pintype "passive+no_connect"))
    )
    (net (code "109") (name "unconnected-(U5C-NC-PadT3)") (class "Default")
      (node (ref "U5") (pin "T3") (pinfunction "NC_T3") (pintype "passive+no_connect"))
    )
    (net (code "110") (name "unconnected-(U5C-NC-PadT7)") (class "Default")
      (node (ref "U5") (pin "T7") (pinfunction "NC_T7") (pintype "passive+no_connect"))
    )
  )
)
